# xplained-add-on-board-rev0.net
KiCad netlist of a schematic drawn in EAGLE
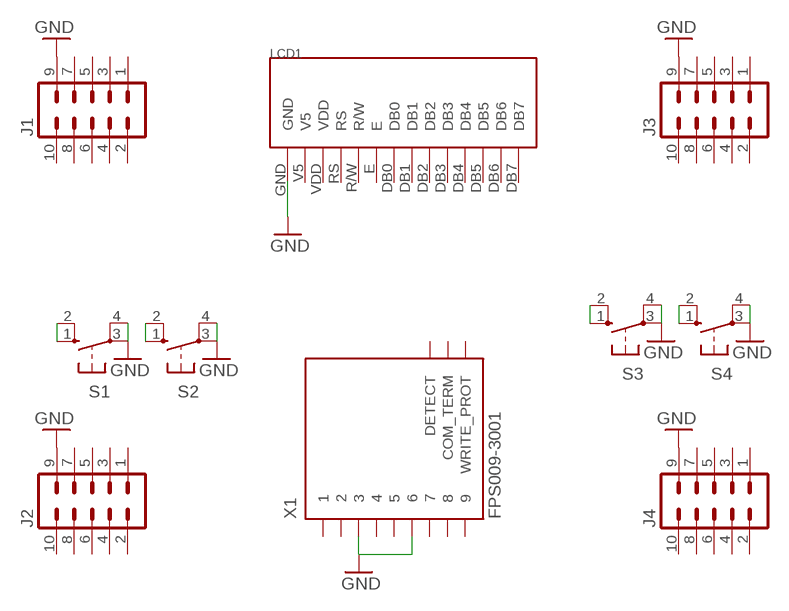
[diagram p0: schematic, sheet 1]

(export (version "E")
  (design (tool "Eeschema 10.0.6"))
  (components
    (comp (ref "J1")
      (value "ML10")
      (footprint "eagle-import:ML10")
      (libsource (lib "eagle-import") (part "ML10"))
    )
    (comp (ref "J2")
      (value "ML10")
      (footprint "eagle-import:ML10")
      (libsource (lib "eagle-import") (part "ML10"))
    )
    (comp (ref "J3")
      (value "ML10")
      (footprint "eagle-import:ML10")
      (libsource (lib "eagle-import") (part "ML10"))
    )
    (comp (ref "J4")
      (value "ML10")
      (footprint "eagle-import:ML10")
      (libsource (lib "eagle-import") (part "ML10"))
    )
    (comp (ref "LCD1")
      (value "NHD-C0220AA-FSW-FTW")
      (footprint "eagle-import:NHD-C0220AA-FSW-FTW")
      (libsource (lib "eagle-import") (part "NHD-C0220AA-FSW-FTW"))
    )
    (comp (ref "S1")
      (value "10-XX")
      (footprint "eagle-import:B3F-10XX")
      (fields (field (name "MPN") "B3F-1000"))
      (libsource (lib "eagle-import") (part "10-XX"))
    )
    (comp (ref "S2")
      (value "10-XX")
      (footprint "eagle-import:B3F-10XX")
      (fields (field (name "MPN") "B3F-1000"))
      (libsource (lib "eagle-import") (part "10-XX"))
    )
    (comp (ref "S3")
      (value "10-XX")
      (footprint "eagle-import:B3F-10XX")
      (fields (field (name "MPN") "B3F-1000"))
      (libsource (lib "eagle-import") (part "10-XX"))
    )
    (comp (ref "S4")
      (value "10-XX")
      (footprint "eagle-import:B3F-10XX")
      (fields (field (name "MPN") "B3F-1000"))
      (libsource (lib "eagle-import") (part "10-XX"))
    )
    (comp (ref "X1")
      (value "FPS009-3001")
      (footprint "eagle-import:FPS009-3000")
      (fields (field (name "MPN") "FPS009-3001-BL"))
      (libsource (lib "eagle-import") (part "FPS009-3001"))
    )
  )
  (nets
    (net (code "1") (name "GND") (class "Default")
      (node (ref "J1") (pin "9") (pinfunction "9_9") (pintype "passive"))
      (node (ref "J2") (pin "9") (pinfunction "9_9") (pintype "passive"))
      (node (ref "J3") (pin "9") (pinfunction "9_9") (pintype "passive"))
      (node (ref "J4") (pin "9") (pinfunction "9_9") (pintype "passive"))
      (node (ref "S1") (pin "3") (pinfunction "P_3") (pintype "passive"))
      (node (ref "S1") (pin "4") (pinfunction "P1_4") (pintype "passive"))
      (node (ref "S2") (pin "3") (pinfunction "P_3") (pintype "passive"))
      (node (ref "S2") (pin "4") (pinfunction "P1_4") (pintype "passive"))
      (node (ref "S3") (pin "3") (pinfunction "P_3") (pintype "passive"))
      (node (ref "S3") (pin "4") (pinfunction "P1_4") (pintype "passive"))
      (node (ref "S4") (pin "3") (pinfunction "P_3") (pintype "passive"))
      (node (ref "S4") (pin "4") (pinfunction "P1_4") (pintype "passive"))
      (node (ref "X1") (pin "3") (pinfunction "3_3") (pintype "input"))
      (node (ref "X1") (pin "6") (pinfunction "6_6") (pintype "input"))
    )
    (net (code "2") (name "Net-(S1-S)") (class "Default")
      (node (ref "S1") (pin "1") (pinfunction "S_1") (pintype "passive"))
      (node (ref "S1") (pin "2") (pinfunction "S1_2") (pintype "passive"))
    )
    (net (code "3") (name "Net-(S2-S)") (class "Default")
      (node (ref "S2") (pin "1") (pinfunction "S_1") (pintype "passive"))
      (node (ref "S2") (pin "2") (pinfunction "S1_2") (pintype "passive"))
    )
    (net (code "4") (name "Net-(S3-S)") (class "Default")
      (node (ref "S3") (pin "1") (pinfunction "S_1") (pintype "passive"))
      (node (ref "S3") (pin "2") (pinfunction "S1_2") (pintype "passive"))
    )
    (net (code "5") (name "Net-(S4-S)") (class "Default")
      (node (ref "S4") (pin "1") (pinfunction "S_1") (pintype "passive"))
      (node (ref "S4") (pin "2") (pinfunction "S1_2") (pintype "passive"))
    )
    (net (code "6") (name "unconnected-(J1-Pad1)") (class "Default")
      (node (ref "J1") (pin "1") (pinfunction "1_1") (pintype "passive"))
    )
    (net (code "7") (name "unconnected-(J1-Pad2)") (class "Default")
      (node (ref "J1") (pin "2") (pinfunction "2_2") (pintype "passive"))
    )
    (net (code "8") (name "unconnected-(J1-Pad3)") (class "Default")
      (node (ref "J1") (pin "3") (pinfunction "3_3") (pintype "passive"))
    )
    (net (code "9") (name "unconnected-(J1-Pad4)") (class "Default")
      (node (ref "J1") (pin "4") (pinfunction "4_4") (pintype "passive"))
    )
    (net (code "10") (name "unconnected-(J1-Pad5)") (class "Default")
      (node (ref "J1") (pin "5") (pinfunction "5_5") (pintype "passive"))
    )
    (net (code "11") (name "unconnected-(J1-Pad6)") (class "Default")
      (node (ref "J1") (pin "6") (pinfunction "6_6") (pintype "passive"))
    )
    (net (code "12") (name "unconnected-(J1-Pad7)") (class "Default")
      (node (ref "J1") (pin "7") (pinfunction "7_7") (pintype "passive"))
    )
    (net (code "13") (name "unconnected-(J1-Pad8)") (class "Default")
      (node (ref "J1") (pin "8") (pinfunction "8_8") (pintype "passive"))
    )
    (net (code "14") (name "unconnected-(J1-Pad10)") (class "Default")
      (node (ref "J1") (pin "10") (pinfunction "10_10") (pintype "passive"))
    )
    (net (code "15") (name "unconnected-(J2-Pad1)") (class "Default")
      (node (ref "J2") (pin "1") (pinfunction "1_1") (pintype "passive"))
    )
    (net (code "16") (name "unconnected-(J2-Pad2)") (class "Default")
      (node (ref "J2") (pin "2") (pinfunction "2_2") (pintype "passive"))
    )
    (net (code "17") (name "unconnected-(J2-Pad3)") (class "Default")
      (node (ref "J2") (pin "3") (pinfunction "3_3") (pintype "passive"))
    )
    (net (code "18") (name "unconnected-(J2-Pad4)") (class "Default")
      (node (ref "J2") (pin "4") (pinfunction "4_4") (pintype "passive"))
    )
    (net (code "19") (name "unconnected-(J2-Pad5)") (class "Default")
      (node (ref "J2") (pin "5") (pinfunction "5_5") (pintype "passive"))
    )
    (net (code "20") (name "unconnected-(J2-Pad6)") (class "Default")
      (node (ref "J2") (pin "6") (pinfunction "6_6") (pintype "passive"))
    )
    (net (code "21") (name "unconnected-(J2-Pad7)") (class "Default")
      (node (ref "J2") (pin "7") (pinfunction "7_7") (pintype "passive"))
    )
    (net (code "22") (name "unconnected-(J2-Pad8)") (class "Default")
      (node (ref "J2") (pin "8") (pinfunction "8_8") (pintype "passive"))
    )
    (net (code "23") (name "unconnected-(J2-Pad10)") (class "Default")
      (node (ref "J2") (pin "10") (pinfunction "10_10") (pintype "passive"))
    )
    (net (code "24") (name "unconnected-(J3-Pad1)") (class "Default")
      (node (ref "J3") (pin "1") (pinfunction "1_1") (pintype "passive"))
    )
    (net (code "25") (name "unconnected-(J3-Pad2)") (class "Default")
      (node (ref "J3") (pin "2") (pinfunction "2_2") (pintype "passive"))
    )
    (net (code "26") (name "unconnected-(J3-Pad3)") (class "Default")
      (node (ref "J3") (pin "3") (pinfunction "3_3") (pintype "passive"))
    )
    (net (code "27") (name "unconnected-(J3-Pad4)") (class "Default")
      (node (ref "J3") (pin "4") (pinfunction "4_4") (pintype "passive"))
    )
    (net (code "28") (name "unconnected-(J3-Pad5)") (class "Default")
      (node (ref "J3") (pin "5") (pinfunction "5_5") (pintype "passive"))
    )
    (net (code "29") (name "unconnected-(J3-Pad6)") (class "Default")
      (node (ref "J3") (pin "6") (pinfunction "6_6") (pintype "passive"))
    )
    (net (code "30") (name "unconnected-(J3-Pad7)") (class "Default")
      (node (ref "J3") (pin "7") (pinfunction "7_7") (pintype "passive"))
    )
    (net (code "31") (name "unconnected-(J3-Pad8)") (class "Default")
      (node (ref "J3") (pin "8") (pinfunction "8_8") (pintype "passive"))
    )
    (net (code "32") (name "unconnected-(J3-Pad10)") (class "Default")
      (node (ref "J3") (pin "10") (pinfunction "10_10") (pintype "passive"))
    )
    (net (code "33") (name "unconnected-(J4-Pad1)") (class "Default")
      (node (ref "J4") (pin "1") (pinfunction "1_1") (pintype "passive"))
    )
    (net (code "34") (name "unconnected-(J4-Pad2)") (class "Default")
      (node (ref "J4") (pin "2") (pinfunction "2_2") (pintype "passive"))
    )
    (net (code "35") (name "unconnected-(J4-Pad3)") (class "Default")
      (node (ref "J4") (pin "3") (pinfunction "3_3") (pintype "passive"))
    )
    (net (code "36") (name "unconnected-(J4-Pad4)") (class "Default")
      (node (ref "J4") (pin "4") (pinfunction "4_4") (pintype "passive"))
    )
    (net (code "37") (name "unconnected-(J4-Pad5)") (class "Default")
      (node (ref "J4") (pin "5") (pinfunction "5_5") (pintype "passive"))
    )
    (net (code "38") (name "unconnected-(J4-Pad6)") (class "Default")
      (node (ref "J4") (pin "6") (pinfunction "6_6") (pintype "passive"))
    )
    (net (code "39") (name "unconnected-(J4-Pad7)") (class "Default")
      (node (ref "J4") (pin "7") (pinfunction "7_7") (pintype "passive"))
    )
    (net (code "40") (name "unconnected-(J4-Pad8)") (class "Default")
      (node (ref "J4") (pin "8") (pinfunction "8_8") (pintype "passive"))
    )
    (net (code "41") (name "unconnected-(J4-Pad10)") (class "Default")
      (node (ref "J4") (pin "10") (pinfunction "10_10") (pintype "passive"))
    )
    (net (code "42") (name "unconnected-(LCD1-PadDB0)") (class "Default")
      (node (ref "LCD1") (pin "DB0") (pinfunction "DB0_DB0") (pintype "bidirectional"))
    )
    (net (code "43") (name "unconnected-(LCD1-PadDB1)") (class "Default")
      (node (ref "LCD1") (pin "DB1") (pinfunction "DB1_DB1") (pintype "bidirectional"))
    )
    (net (code "44") (name "unconnected-(LCD1-PadDB2)") (class "Default")
      (node (ref "LCD1") (pin "DB2") (pinfunction "DB2_DB2") (pintype "bidirectional"))
    )
    (net (code "45") (name "unconnected-(LCD1-PadDB3)") (class "Default")
      (node (ref "LCD1") (pin "DB3") (pinfunction "DB3_DB3") (pintype "bidirectional"))
    )
    (net (code "46") (name "unconnected-(LCD1-PadDB4)") (class "Default")
      (node (ref "LCD1") (pin "DB4") (pinfunction "DB4_DB4") (pintype "bidirectional"))
    )
    (net (code "47") (name "unconnected-(LCD1-PadDB5)") (class "Default")
      (node (ref "LCD1") (pin "DB5") (pinfunction "DB5_DB5") (pintype "bidirectional"))
    )
    (net (code "48") (name "unconnected-(LCD1-PadDB6)") (class "Default")
      (node (ref "LCD1") (pin "DB6") (pinfunction "DB6_DB6") (pintype "bidirectional"))
    )
    (net (code "49") (name "unconnected-(LCD1-PadDB7)") (class "Default")
      (node (ref "LCD1") (pin "DB7") (pinfunction "DB7_DB7") (pintype "bidirectional"))
    )
    (net (code "50") (name "unconnected-(LCD1-PadE)") (class "Default")
      (node (ref "LCD1") (pin "E") (pinfunction "E_E") (pintype "bidirectional"))
    )
    (net (code "51") (name "unconnected-(LCD1-PadGND)") (class "Default")
      (node (ref "LCD1") (pin "GND") (pinfunction "GND_GND") (pintype "bidirectional"))
    )
    (net (code "52") (name "unconnected-(LCD1-PadRS)") (class "Default")
      (node (ref "LCD1") (pin "RS") (pinfunction "RS_RS") (pintype "bidirectional"))
    )
    (net (code "53") (name "unconnected-(LCD1-PadR{slash}W)") (class "Default")
      (node (ref "LCD1") (pin "R/W") (pinfunction "R/W_R/W") (pintype "bidirectional"))
    )
    (net (code "54") (name "unconnected-(LCD1-PadV5)") (class "Default")
      (node (ref "LCD1") (pin "V5") (pinfunction "V5_V5") (pintype "bidirectional"))
    )
    (net (code "55") (name "unconnected-(LCD1-PadVDD)") (class "Default")
      (node (ref "LCD1") (pin "VDD") (pinfunction "VDD_VDD") (pintype "bidirectional"))
    )
    (net (code "56") (name "unconnected-(X1-Pad1)") (class "Default")
      (node (ref "X1") (pin "1") (pinfunction "1_1") (pintype "input"))
    )
    (net (code "57") (name "unconnected-(X1-Pad2)") (class "Default")
      (node (ref "X1") (pin "2") (pinfunction "2_2") (pintype "input"))
    )
    (net (code "58") (name "unconnected-(X1-Pad4)") (class "Default")
      (node (ref "X1") (pin "4") (pinfunction "4_4") (pintype "input"))
    )
    (net (code "59") (name "unconnected-(X1-Pad5)") (class "Default")
      (node (ref "X1") (pin "5") (pinfunction "5_5") (pintype "input"))
    )
    (net (code "60") (name "unconnected-(X1-Pad7)") (class "Default")
      (node (ref "X1") (pin "7") (pinfunction "7_7") (pintype "input"))
    )
    (net (code "61") (name "unconnected-(X1-Pad8)") (class "Default")
      (node (ref "X1") (pin "8") (pinfunction "8_8") (pintype "input"))
    )
    (net (code "62") (name "unconnected-(X1-Pad9)") (class "Default")
      (node (ref "X1") (pin "9") (pinfunction "9_9") (pintype "input"))
    )
    (net (code "63") (name "unconnected-(X1-PadCOM_TERM)") (class "Default")
      (node (ref "X1") (pin "COM_TERM") (pinfunction "COM_TERM_COM_TERM") (pintype "input"))
    )
    (net (code "64") (name "unconnected-(X1-PadDETECT)") (class "Default")
      (node (ref "X1") (pin "DETECT") (pinfunction "DETECT_DETECT") (pintype "input"))
    )
    (net (code "65") (name "unconnected-(X1-PadWRITE_PROT)") (class "Default")
      (node (ref "X1") (pin "WRITE_PROT") (pinfunction "WRITE_PROT_WRITE_PROT") (pintype "input"))
    )
  )
)
